# ODGIRON-v1_0-F103-0410.net
KiCad netlist of a schematic drawn in EAGLE
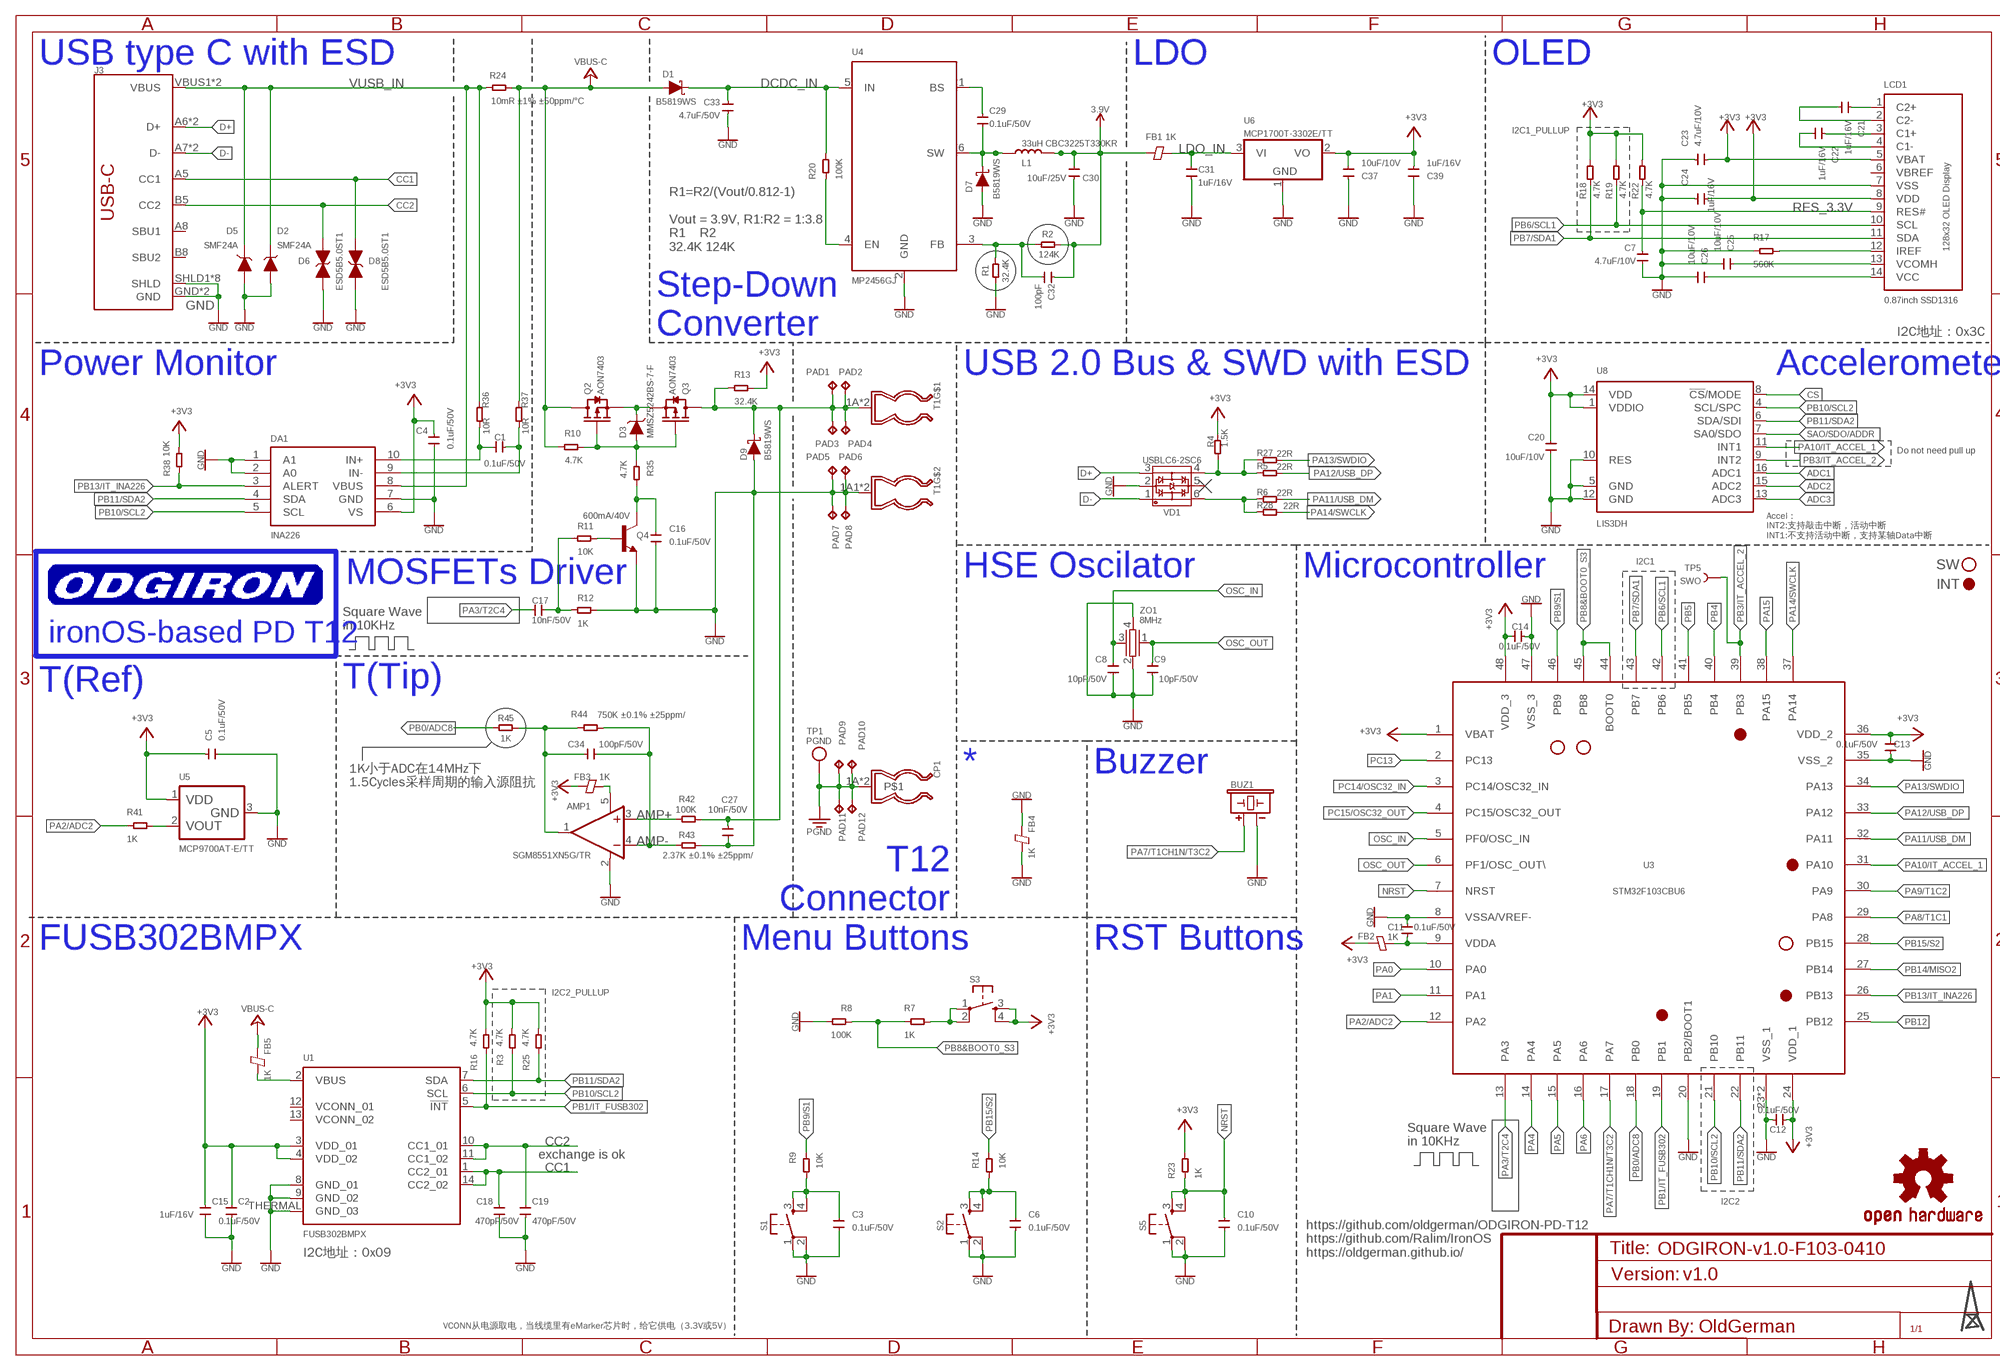
[diagram p0: schematic, sheet 1, part 1 of 2]
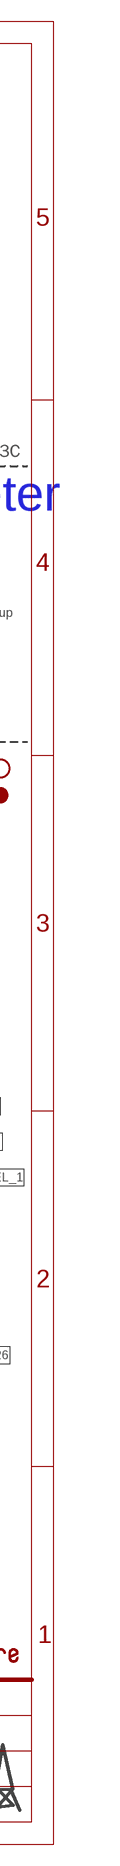
[diagram p1: schematic, sheet 1, part 2 of 2]

(export (version "E")
  (design (tool "Eeschema 10.0.6"))
  (components
    (comp (ref "AMP1")
      (value "SGM8551XN5G/TR")
      (footprint "eagle-import:SOT23-5")
      (fields (field (name "MPN") "OPA340NA/3KG4"))
      (libsource (lib "eagle-import") (part "AMP_SIMGLEN"))
    )
    (comp (ref "BUZ1")
      (value "BUZZERBUZZER_5020")
      (footprint "eagle-import:BUZZER_5020")
      (libsource (lib "eagle-import") (part "BUZZERBUZZER_5020"))
    )
    (comp (ref "C1")
      (value "0.1uF/50V")
      (footprint "eagle-import:C0603")
      (libsource (lib "eagle-import") (part "SEEED_CAP-0603"))
    )
    (comp (ref "C2")
      (value "0.1uF/50V")
      (footprint "eagle-import:C0603")
      (libsource (lib "eagle-import") (part "SEEED_CAP-0603"))
    )
    (comp (ref "C3")
      (value "0.1uF/50V")
      (footprint "eagle-import:C0603")
      (libsource (lib "eagle-import") (part "SEEED_CAP-0603"))
    )
    (comp (ref "C4")
      (value "0.1uF/50V")
      (footprint "eagle-import:C0603")
      (libsource (lib "eagle-import") (part "SEEED_CAP-0603"))
    )
    (comp (ref "C5")
      (value "0.1uF/50V")
      (footprint "eagle-import:C0603")
      (libsource (lib "eagle-import") (part "SEEED_CAP-0603"))
    )
    (comp (ref "C6")
      (value "0.1uF/50V")
      (footprint "eagle-import:C0603")
      (libsource (lib "eagle-import") (part "SEEED_CAP-0603"))
    )
    (comp (ref "C7")
      (value "4.7uF/10V")
      (footprint "eagle-import:C0603")
      (libsource (lib "eagle-import") (part "SEEED_CAP-0603"))
    )
    (comp (ref "C8")
      (value "10pF/50V")
      (footprint "eagle-import:C0603")
      (libsource (lib "eagle-import") (part "SEEED_CAP-0603"))
    )
    (comp (ref "C9")
      (value "10pF/50V")
      (footprint "eagle-import:C0603")
      (libsource (lib "eagle-import") (part "SEEED_CAP-0603"))
    )
    (comp (ref "C10")
      (value "0.1uF/50V")
      (footprint "eagle-import:C0603")
      (libsource (lib "eagle-import") (part "SEEED_CAP-0603"))
    )
    (comp (ref "C11")
      (value "0.1uF/50V")
      (footprint "eagle-import:C0603")
      (libsource (lib "eagle-import") (part "SEEED_CAP-0603"))
    )
    (comp (ref "C12")
      (value "0.1uF/50V")
      (footprint "eagle-import:C0603")
      (libsource (lib "eagle-import") (part "SEEED_CAP-0603"))
    )
    (comp (ref "C13")
      (value "0.1uF/50V")
      (footprint "eagle-import:C0603")
      (libsource (lib "eagle-import") (part "SEEED_CAP-0603"))
    )
    (comp (ref "C14")
      (value "0.1uF/50V")
      (footprint "eagle-import:C0603")
      (libsource (lib "eagle-import") (part "SEEED_CAP-0603"))
    )
    (comp (ref "C15")
      (value "1uF/16V")
      (footprint "eagle-import:C0603")
      (libsource (lib "eagle-import") (part "SEEED_CAP-0603"))
    )
    (comp (ref "C16")
      (value "0.1uF/50V")
      (footprint "eagle-import:C0603")
      (libsource (lib "eagle-import") (part "SEEED_CAP-0603"))
    )
    (comp (ref "C17")
      (value "10nF/50V")
      (footprint "eagle-import:C0603")
      (libsource (lib "eagle-import") (part "SEEED_CAP-0603"))
    )
    (comp (ref "C18")
      (value "470pF/50V")
      (footprint "eagle-import:C0603")
      (libsource (lib "eagle-import") (part "SEEED_CAP-0603"))
    )
    (comp (ref "C19")
      (value "470pF/50V")
      (footprint "eagle-import:C0603")
      (libsource (lib "eagle-import") (part "SEEED_CAP-0603"))
    )
    (comp (ref "C20")
      (value "10uF/10V")
      (footprint "eagle-import:C0603")
      (libsource (lib "eagle-import") (part "SEEED_CAP-0603"))
    )
    (comp (ref "C21")
      (value "1uF/16V")
      (footprint "eagle-import:C0603")
      (libsource (lib "eagle-import") (part "SEEED_CAP-0603"))
    )
    (comp (ref "C22")
      (value "1uF/16V")
      (footprint "eagle-import:C0603")
      (libsource (lib "eagle-import") (part "SEEED_CAP-0603"))
    )
    (comp (ref "C23")
      (value "4.7uF/10V")
      (footprint "eagle-import:C0603")
      (libsource (lib "eagle-import") (part "SEEED_CAP-0603"))
    )
    (comp (ref "C24")
      (value "1uF/16V")
      (footprint "eagle-import:C0603")
      (libsource (lib "eagle-import") (part "SEEED_CAP-0603"))
    )
    (comp (ref "C25")
      (value "10uF/10V")
      (footprint "eagle-import:C0603")
      (libsource (lib "eagle-import") (part "SEEED_CAP-0603"))
    )
    (comp (ref "C26")
      (value "10uF/10V")
      (footprint "eagle-import:C0603")
      (libsource (lib "eagle-import") (part "SEEED_CAP-0603"))
    )
    (comp (ref "C27")
      (value "10nF/50V")
      (footprint "eagle-import:C0603")
      (libsource (lib "eagle-import") (part "SEEED_CAP-0603"))
    )
    (comp (ref "C29")
      (value "0.1uF/50V")
      (footprint "eagle-import:C0603")
      (libsource (lib "eagle-import") (part "SEEED_CAP-0603"))
    )
    (comp (ref "C30")
      (value "10uF/25V")
      (footprint "eagle-import:C0805")
      (libsource (lib "eagle-import") (part "SEEED_CAP-0805"))
    )
    (comp (ref "C31")
      (value "1uF/16V")
      (footprint "eagle-import:C0603")
      (libsource (lib "eagle-import") (part "SEEED_CAP-0603"))
    )
    (comp (ref "C32")
      (value "100pF")
      (footprint "eagle-import:C0603")
      (libsource (lib "eagle-import") (part "SEEED_CAP-0603"))
    )
    (comp (ref "C33")
      (value "4.7uF/50V")
      (footprint "eagle-import:C0805")
      (libsource (lib "eagle-import") (part "SEEED_CAP-0805"))
    )
    (comp (ref "C34")
      (value "100pF/50V")
      (footprint "eagle-import:C0603")
      (libsource (lib "eagle-import") (part "SEEED_CAP-0603"))
    )
    (comp (ref "C37")
      (value "10uF/10V")
      (footprint "eagle-import:C0603")
      (libsource (lib "eagle-import") (part "SEEED_CAP-0603"))
    )
    (comp (ref "C39")
      (value "1uF/16V")
      (footprint "eagle-import:C0603")
      (libsource (lib "eagle-import") (part "SEEED_CAP-0603"))
    )
    (comp (ref "CP1")
      (value "FUSE_CLIPS_01")
      (footprint "eagle-import:FUSE_CLIPS_01")
      (libsource (lib "eagle-import") (part "FUSE_CLIPS_01"))
    )
    (comp (ref "D1")
      (value "B5819WS")
      (footprint "eagle-import:SOD-323")
      (libsource (lib "eagle-import") (part "DIODE_SCHOTTKYSOD323"))
    )
    (comp (ref "D2")
      (value "SMF24A")
      (footprint "eagle-import:SOD-123")
      (libsource (lib "eagle-import") (part "DIODE-TVS_UNIDIRECTIONALSOD-123"))
    )
    (comp (ref "D3")
      (value "MMSZ5242BS-7-F")
      (footprint "eagle-import:SOD-323")
      (libsource (lib "eagle-import") (part "DIODE_ZENERSOD-323"))
    )
    (comp (ref "D5")
      (value "SMF24A")
      (footprint "eagle-import:SOD-123")
      (libsource (lib "eagle-import") (part "DIODE-TVS_UNIDIRECTIONALSOD-123"))
    )
    (comp (ref "D6")
      (value "ESD5B5.0ST1")
      (footprint "eagle-import:SOD-523")
      (libsource (lib "eagle-import") (part "DIODE-TVS_BI−DIRECTIONALSOD-523"))
    )
    (comp (ref "D7")
      (value "B5819WS")
      (footprint "eagle-import:SOD-323")
      (libsource (lib "eagle-import") (part "DIODE_SCHOTTKYSOD323"))
    )
    (comp (ref "D8")
      (value "ESD5B5.0ST1")
      (footprint "eagle-import:SOD-523")
      (libsource (lib "eagle-import") (part "DIODE-TVS_BI−DIRECTIONALSOD-523"))
    )
    (comp (ref "D9")
      (value "B5819WS")
      (footprint "eagle-import:SOD-323")
      (libsource (lib "eagle-import") (part "DIODE_SCHOTTKYSOD323"))
    )
    (comp (ref "DA1")
      (value "INA226")
      (footprint "eagle-import:MSOP10")
      (libsource (lib "eagle-import") (part "INA226"))
    )
    (comp (ref "FB1")
      (value "1K")
      (footprint "eagle-import:F0603")
      (libsource (lib "eagle-import") (part "FERRITE-BEAD-0603"))
    )
    (comp (ref "FB2")
      (value "1K")
      (footprint "eagle-import:F0603")
      (libsource (lib "eagle-import") (part "FERRITE-BEAD-0603"))
    )
    (comp (ref "FB3")
      (value "1K")
      (footprint "eagle-import:F0603")
      (libsource (lib "eagle-import") (part "FERRITE-BEAD-0603"))
    )
    (comp (ref "FB4")
      (value "1K")
      (footprint "eagle-import:F0603")
      (libsource (lib "eagle-import") (part "FERRITE-BEAD-0603"))
    )
    (comp (ref "FB5")
      (value "1K")
      (footprint "eagle-import:F0603")
      (libsource (lib "eagle-import") (part "FERRITE-BEAD-0603"))
    )
    (comp (ref "J3")
      (value "USB_C_LONG-SYMBOL2-LAYER")
      (footprint "eagle-import:USB-C-16P")
      (libsource (lib "eagle-import") (part "USB_C_LONG-SYMBOL2-LAYER"))
    )
    (comp (ref "L1")
      (value "33uH CBC3225T330KR")
      (footprint "eagle-import:SMD,3.2X2.5X2.5MM")
      (libsource (lib "eagle-import") (part "INDUCTOR3225"))
    )
    (comp (ref "LCD1")
      (value "0.87inch SSD1316")
      (footprint "eagle-import:0.87INCH_128X32_OLED_SSD1306")
      (libsource (lib "eagle-import") (part "0.87INCH_OLED_128X32_SSD1306"))
    )
    (comp (ref "LOGO1")
      (value "OSHW-LOGONO_SILK")
      (footprint "eagle-import:DUMMY")
      (libsource (lib "eagle-import") (part "OSHW-LOGONO_SILK"))
    )
    (comp (ref "PAD1")
      (value "PADTP16SQ")
      (footprint "eagle-import:TP16SQ")
      (libsource (lib "eagle-import") (part "PADTP16SQ"))
    )
    (comp (ref "PAD2")
      (value "PADTP16SQ")
      (footprint "eagle-import:TP16SQ")
      (libsource (lib "eagle-import") (part "PADTP16SQ"))
    )
    (comp (ref "PAD3")
      (value "PADTP16SQ")
      (footprint "eagle-import:TP16SQ")
      (libsource (lib "eagle-import") (part "PADTP16SQ"))
    )
    (comp (ref "PAD4")
      (value "PADTP16SQ")
      (footprint "eagle-import:TP16SQ")
      (libsource (lib "eagle-import") (part "PADTP16SQ"))
    )
    (comp (ref "PAD5")
      (value "PADTP16SQ")
      (footprint "eagle-import:TP16SQ")
      (libsource (lib "eagle-import") (part "PADTP16SQ"))
    )
    (comp (ref "PAD6")
      (value "PADTP16SQ")
      (footprint "eagle-import:TP16SQ")
      (libsource (lib "eagle-import") (part "PADTP16SQ"))
    )
    (comp (ref "PAD7")
      (value "PADTP16SQ")
      (footprint "eagle-import:TP16SQ")
      (libsource (lib "eagle-import") (part "PADTP16SQ"))
    )
    (comp (ref "PAD8")
      (value "PADTP16SQ")
      (footprint "eagle-import:TP16SQ")
      (libsource (lib "eagle-import") (part "PADTP16SQ"))
    )
    (comp (ref "PAD9")
      (value "PADTP16SQ")
      (footprint "eagle-import:TP16SQ")
      (libsource (lib "eagle-import") (part "PADTP16SQ"))
    )
    (comp (ref "PAD10")
      (value "PADTP16SQ")
      (footprint "eagle-import:TP16SQ")
      (libsource (lib "eagle-import") (part "PADTP16SQ"))
    )
    (comp (ref "PAD11")
      (value "PADTP16SQ")
      (footprint "eagle-import:TP16SQ")
      (libsource (lib "eagle-import") (part "PADTP16SQ"))
    )
    (comp (ref "PAD12")
      (value "PADTP16SQ")
      (footprint "eagle-import:TP16SQ")
      (libsource (lib "eagle-import") (part "PADTP16SQ"))
    )
    (comp (ref "Q2")
      (value "AON7403")
      (footprint "eagle-import:DFN8P-0.65-3X3X0.8MM")
      (libsource (lib "eagle-import") (part "MOSFET-P-AON7403"))
    )
    (comp (ref "Q3")
      (value "AON7403")
      (footprint "eagle-import:DFN8P-0.65-3X3X0.8MM")
      (libsource (lib "eagle-import") (part "MOSFET-P-AON7403"))
    )
    (comp (ref "Q4")
      (value "600mA/40V")
      (footprint "eagle-import:SOT23-3")
      (libsource (lib "eagle-import") (part "TRANS_NPN-MMBT2222AL"))
    )
    (comp (ref "R1")
      (value "32.4K")
      (footprint "eagle-import:R0603")
      (libsource (lib "eagle-import") (part "SEEED_RES-0603"))
    )
    (comp (ref "R2")
      (value "124K")
      (footprint "eagle-import:R0603")
      (libsource (lib "eagle-import") (part "SEEED_RES-0603"))
    )
    (comp (ref "R3")
      (value "4.7K")
      (footprint "eagle-import:R0603")
      (libsource (lib "eagle-import") (part "SEEED_RES-0603"))
    )
    (comp (ref "R4")
      (value "1.5K")
      (footprint "eagle-import:R0603")
      (libsource (lib "eagle-import") (part "SEEED_RES-0603"))
    )
    (comp (ref "R5")
      (value "22R")
      (footprint "eagle-import:R0603")
      (libsource (lib "eagle-import") (part "SEEED_RES-0603"))
    )
    (comp (ref "R6")
      (value "22R")
      (footprint "eagle-import:R0603")
      (libsource (lib "eagle-import") (part "SEEED_RES-0603"))
    )
    (comp (ref "R7")
      (value "1K")
      (footprint "eagle-import:R0603")
      (libsource (lib "eagle-import") (part "SEEED_RES-0603"))
    )
    (comp (ref "R8")
      (value "100K")
      (footprint "eagle-import:R0603")
      (libsource (lib "eagle-import") (part "SEEED_RES-0603"))
    )
    (comp (ref "R9")
      (value "10K")
      (footprint "eagle-import:R0603")
      (libsource (lib "eagle-import") (part "SEEED_RES-0603"))
    )
    (comp (ref "R10")
      (value "4.7K")
      (footprint "eagle-import:R0603")
      (libsource (lib "eagle-import") (part "SEEED_RES-0603"))
    )
    (comp (ref "R11")
      (value "10K")
      (footprint "eagle-import:R0603")
      (libsource (lib "eagle-import") (part "SEEED_RES-0603"))
    )
    (comp (ref "R12")
      (value "1K")
      (footprint "eagle-import:R0603")
      (libsource (lib "eagle-import") (part "SEEED_RES-0603"))
    )
    (comp (ref "R13")
      (value "32.4K")
      (footprint "eagle-import:R0603")
      (libsource (lib "eagle-import") (part "SEEED_RES-0603"))
    )
    (comp (ref "R14")
      (value "10K")
      (footprint "eagle-import:R0603")
      (libsource (lib "eagle-import") (part "SEEED_RES-0603"))
    )
    (comp (ref "R16")
      (value "4.7K")
      (footprint "eagle-import:R0603")
      (libsource (lib "eagle-import") (part "SEEED_RES-0603"))
    )
    (comp (ref "R17")
      (value "560K")
      (footprint "eagle-import:R0603")
      (libsource (lib "eagle-import") (part "SEEED_RES-0603"))
    )
    (comp (ref "R18")
      (value "4.7K")
      (footprint "eagle-import:R0603")
      (libsource (lib "eagle-import") (part "SEEED_RES-0603"))
    )
    (comp (ref "R19")
      (value "4.7K")
      (footprint "eagle-import:R0603")
      (libsource (lib "eagle-import") (part "SEEED_RES-0603"))
    )
    (comp (ref "R20")
      (value "100K")
      (footprint "eagle-import:R0603")
      (libsource (lib "eagle-import") (part "SEEED_RES-0603"))
    )
    (comp (ref "R22")
      (value "4.7K")
      (footprint "eagle-import:R0603")
      (libsource (lib "eagle-import") (part "SEEED_RES-0603"))
    )
    (comp (ref "R23")
      (value "1K")
      (footprint "eagle-import:R0603")
      (libsource (lib "eagle-import") (part "SEEED_RES-0603"))
    )
    (comp (ref "R24")
      (value "10mR ±1% ±50ppm/°C")
      (footprint "eagle-import:R1206")
      (libsource (lib "eagle-import") (part "SEEED_RES-1206"))
    )
    (comp (ref "R25")
      (value "4.7K")
      (footprint "eagle-import:R0603")
      (libsource (lib "eagle-import") (part "SEEED_RES-0603"))
    )
    (comp (ref "R27")
      (value "22R")
      (footprint "eagle-import:R0603")
      (libsource (lib "eagle-import") (part "SEEED_RES-0603"))
    )
    (comp (ref "R28")
      (value "22R")
      (footprint "eagle-import:R0603")
      (libsource (lib "eagle-import") (part "SEEED_RES-0603"))
    )
    (comp (ref "R35")
      (value "4.7K")
      (footprint "eagle-import:R0603")
      (libsource (lib "eagle-import") (part "SEEED_RES-0603"))
    )
    (comp (ref "R36")
      (value "10R")
      (footprint "eagle-import:R0603")
      (libsource (lib "eagle-import") (part "SEEED_RES-0603"))
    )
    (comp (ref "R37")
      (value "10R")
      (footprint "eagle-import:R0603")
      (libsource (lib "eagle-import") (part "SEEED_RES-0603"))
    )
    (comp (ref "R38")
      (value "10K")
      (footprint "eagle-import:R0603")
      (libsource (lib "eagle-import") (part "SEEED_RES-0603"))
    )
    (comp (ref "R41")
      (value "1K")
      (footprint "eagle-import:R0603")
      (libsource (lib "eagle-import") (part "SEEED_RES-0603"))
    )
    (comp (ref "R42")
      (value "100K")
      (footprint "eagle-import:R0603")
      (libsource (lib "eagle-import") (part "SEEED_RES-0603"))
    )
    (comp (ref "R43")
      (value "2.37K ±0.1% ±25ppm/℃")
      (footprint "eagle-import:R0603")
      (libsource (lib "eagle-import") (part "SEEED_RES-0603"))
    )
    (comp (ref "R44")
      (value "750K ±0.1% ±25ppm/℃")
      (footprint "eagle-import:R0603")
      (libsource (lib "eagle-import") (part "SEEED_RES-0603"))
    )
    (comp (ref "R45")
      (value "1K")
      (footprint "eagle-import:R0603")
      (libsource (lib "eagle-import") (part "SEEED_RES-0603"))
    )
    (comp (ref "S1")
      (value "TAC_SWITCHSMD")
      (footprint "eagle-import:TACTILE_SWITCH_SMD")
      (libsource (lib "eagle-import") (part "TAC_SWITCHSMD"))
    )
    (comp (ref "S2")
      (value "TAC_SWITCHSMD")
      (footprint "eagle-import:TACTILE_SWITCH_SMD")
      (libsource (lib "eagle-import") (part "TAC_SWITCHSMD"))
    )
    (comp (ref "S3")
      (value "TAC_SWITCHSMD")
      (footprint "eagle-import:TACTILE_SWITCH_SMD")
      (libsource (lib "eagle-import") (part "TAC_SWITCHSMD"))
    )
    (comp (ref "S5")
      (value "TAC_SWITCHSMD")
      (footprint "eagle-import:TACTILE_SWITCH_SMD")
      (libsource (lib "eagle-import") (part "untitled_TAC_SWITCHSMD"))
    )
    (comp (ref "T1")
      (value "HAKKO_T12_K-TYPE_WITH_FUSE_CLIPS_X2")
      (footprint "eagle-import:HAKKO_T12_K-TYPE_WITH_FUSE_CLIPS_X2")
      (libsource (lib "eagle-import") (part "HAKKO_T12_K-TYPE_WITH_FUSE_CLIPS_X2"))
    )
    (comp (ref "TP1")
      (value "PGND")
      (footprint "eagle-import:TESTPOINT_ROUND_2MM")
      (libsource (lib "eagle-import") (part "TESTPOINTROUND2MM"))
    )
    (comp (ref "TP5")
      (value "SWO")
      (footprint "eagle-import:PAD.03X.03")
      (libsource (lib "eagle-import") (part "TEST-POINT3"))
    )
    (comp (ref "U1")
      (value "FUSB302BMPX")
      (footprint "eagle-import:QFN14-2.5X2.5MM")
      (libsource (lib "eagle-import") (part "FUSB302"))
    )
    (comp (ref "U3")
      (value "STM32F103CBU6")
      (footprint "eagle-import:QFN48_7X7MM_0.5MM")
      (libsource (lib "eagle-import") (part "STM32F1_QFN48"))
    )
    (comp (ref "U4")
      (value "MP2456GJ")
      (footprint "eagle-import:SOT23-6")
      (libsource (lib "eagle-import") (part "MP2456"))
    )
    (comp (ref "U5")
      (value "MCP9700AT-E/TT")
      (footprint "eagle-import:SOT23-3@1")
      (libsource (lib "eagle-import") (part "MCP9700"))
    )
    (comp (ref "U6")
      (value "MCP1700T-3302E/TT")
      (footprint "eagle-import:SOT23-3")
      (libsource (lib "eagle-import") (part "MCP1700"))
    )
    (comp (ref "U8")
      (value "LIS3DH")
      (footprint "eagle-import:LGA-16-3X3")
      (libsource (lib "eagle-import") (part "LIS3DH"))
    )
    (comp (ref "VD1")
      (value "USBLC6-2SC6")
      (footprint "eagle-import:SOT23-6")
      (libsource (lib "eagle-import") (part "USBLC6-2SOT23-6"))
    )
    (comp (ref "ZO1")
      (value "8MHz")
      (footprint "eagle-import:3.2X2.5_KX-7")
      (libsource (lib "eagle-import") (part "3225_CRYSTALL"))
    )
  )
  (nets
    (net (code "1") (name "+3V3") (class "Default")
      (node (ref "C12") (pin "2") (pinfunction "P$2_2") (pintype "passive"))
      (node (ref "C13") (pin "2") (pinfunction "P$2_2") (pintype "passive"))
      (node (ref "C14") (pin "2") (pinfunction "P$2_2") (pintype "passive"))
      (node (ref "C15") (pin "1") (pinfunction "P$1_1") (pintype "passive"))
      (node (ref "C2") (pin "1") (pinfunction "P$1_1") (pintype "passive"))
      (node (ref "C20") (pin "2") (pinfunction "P$2_2") (pintype "passive"))
      (node (ref "C23") (pin "2") (pinfunction "P$2_2") (pintype "passive"))
      (node (ref "C24") (pin "2") (pinfunction "P$2_2") (pintype "passive"))
      (node (ref "C37") (pin "2") (pinfunction "P$2_2") (pintype "passive"))
      (node (ref "C39") (pin "2") (pinfunction "P$2_2") (pintype "passive"))
      (node (ref "C4") (pin "1") (pinfunction "P$1_1") (pintype "passive"))
      (node (ref "C5") (pin "1") (pinfunction "P$1_1") (pintype "passive"))
      (node (ref "DA1") (pin "6") (pinfunction "VS_6") (pintype "bidirectional"))
      (node (ref "FB2") (pin "2") (pinfunction "2_2") (pintype "bidirectional"))
      (node (ref "FB3") (pin "2") (pinfunction "2_2") (pintype "bidirectional"))
      (node (ref "LCD1") (pin "5") (pinfunction "VBAT_5") (pintype "power_in"))
      (node (ref "LCD1") (pin "8") (pinfunction "VDD_8") (pintype "power_in"))
      (node (ref "R13") (pin "2") (pinfunction "2_2") (pintype "passive"))
      (node (ref "R16") (pin "1") (pinfunction "1_1") (pintype "passive"))
      (node (ref "R18") (pin "2") (pinfunction "2_2") (pintype "passive"))
      (node (ref "R19") (pin "2") (pinfunction "2_2") (pintype "passive"))
      (node (ref "R22") (pin "2") (pinfunction "2_2") (pintype "passive"))
      (node (ref "R23") (pin "2") (pinfunction "2_2") (pintype "passive"))
      (node (ref "R25") (pin "1") (pinfunction "1_1") (pintype "passive"))
      (node (ref "R3") (pin "1") (pinfunction "1_1") (pintype "passive"))
      (node (ref "R38") (pin "1") (pinfunction "1_1") (pintype "passive"))
      (node (ref "R4") (pin "2") (pinfunction "2_2") (pintype "passive"))
      (node (ref "S3") (pin "3") (pinfunction "3_3") (pintype "passive"))
      (node (ref "S3") (pin "4") (pinfunction "4_4") (pintype "passive"))
      (node (ref "U1") (pin "3") (pinfunction "VDD_01_3") (pintype "bidirectional"))
      (node (ref "U1") (pin "4") (pinfunction "VDD_02_4") (pintype "bidirectional"))
      (node (ref "U3") (pin "1") (pinfunction "VBAT_1") (pintype "bidirectional"))
      (node (ref "U3") (pin "24") (pinfunction "VDD_1_24") (pintype "bidirectional"))
      (node (ref "U3") (pin "36") (pinfunction "VDD_2_36") (pintype "bidirectional"))
      (node (ref "U3") (pin "48") (pinfunction "VDD_3_48") (pintype "bidirectional"))
      (node (ref "U5") (pin "1") (pinfunction "VDD_1") (pintype "input"))
      (node (ref "U6") (pin "2") (pinfunction "VO_2") (pintype "passive"))
      (node (ref "U8") (pin "1") (pinfunction "VDDIO_1") (pintype "bidirectional"))
      (node (ref "U8") (pin "14") (pinfunction "VDD_14") (pintype "bidirectional"))
    )
    (net (code "2") (name "/AMP+") (class "Default")
      (node (ref "AMP1") (pin "3") (pinfunction "+IN_3") (pintype "input"))
      (node (ref "R42") (pin "1") (pinfunction "1_1") (pintype "passive"))
    )
    (net (code "3") (name "/AMP-") (class "Default")
      (node (ref "AMP1") (pin "4") (pinfunction "-IN_4") (pintype "input"))
      (node (ref "C34") (pin "2") (pinfunction "P$2_2") (pintype "passive"))
      (node (ref "R43") (pin "1") (pinfunction "1_1") (pintype "passive"))
      (node (ref "R44") (pin "2") (pinfunction "2_2") (pintype "passive"))
    )
    (net (code "4") (name "/DCDC_IN") (class "Default")
      (node (ref "C33") (pin "1") (pinfunction "P$1_1") (pintype "passive"))
      (node (ref "D1") (pin "C") (pinfunction "C_C") (pintype "passive"))
      (node (ref "R20") (pin "2") (pinfunction "2_2") (pintype "passive"))
      (node (ref "U4") (pin "5") (pinfunction "IN_5") (pintype "bidirectional"))
    )
    (net (code "5") (name "/LDO_IN") (class "Default")
      (node (ref "C31") (pin "2") (pinfunction "P$2_2") (pintype "passive"))
      (node (ref "FB1") (pin "2") (pinfunction "2_2") (pintype "bidirectional"))
      (node (ref "U6") (pin "3") (pinfunction "VI_3") (pintype "input"))
    )
    (net (code "6") (name "/RES_3.3V") (class "Default")
      (node (ref "C7") (pin "1") (pinfunction "P$1_1") (pintype "passive"))
      (node (ref "LCD1") (pin "9") (pinfunction "RES#_9") (pintype "bidirectional"))
      (node (ref "R22") (pin "1") (pinfunction "1_1") (pintype "passive"))
    )
    (net (code "7") (name "/VBREF") (class "Default")
      (node (ref "LCD1") (pin "6") (pinfunction "VBREF_6") (pintype "power_in"))
    )
    (net (code "8") (name "/VUSB_IN") (class "Default")
      (node (ref "D2") (pin "C") (pinfunction "K_C") (pintype "passive"))
      (node (ref "D5") (pin "C") (pinfunction "K_C") (pintype "passive"))
      (node (ref "DA1") (pin "8") (pinfunction "VBUS_8") (pintype "bidirectional"))
      (node (ref "J3") (pin "VBUS1") (pinfunction "VBUS_VBUS1") (pintype "bidirectional"))
      (node (ref "J3") (pin "VBUS2") (pinfunction "VBUS_VBUS2") (pintype "bidirectional"))
      (node (ref "R24") (pin "2") (pinfunction "2_2") (pintype "passive"))
      (node (ref "R36") (pin "2") (pinfunction "2_2") (pintype "passive"))
    )
    (net (code "9") (name "3.9V") (class "Default")
      (node (ref "C30") (pin "1") (pinfunction "P$1_1") (pintype "passive"))
      (node (ref "C32") (pin "1") (pinfunction "P$1_1") (pintype "passive"))
      (node (ref "FB1") (pin "1") (pinfunction "1_1") (pintype "bidirectional"))
      (node (ref "L1") (pin "2") (pinfunction "2_2") (pintype "passive"))
      (node (ref "R2") (pin "1") (pinfunction "1_1") (pintype "passive"))
    )
    (net (code "10") (name "ADC1") (class "Default")
      (node (ref "U8") (pin "16") (pinfunction "ADC1_16") (pintype "bidirectional"))
    )
    (net (code "11") (name "ADC2") (class "Default")
      (node (ref "U8") (pin "15") (pinfunction "ADC2_15") (pintype "bidirectional"))
    )
    (net (code "12") (name "ADC3") (class "Default")
      (node (ref "U8") (pin "13") (pinfunction "ADC3_13") (pintype "bidirectional"))
    )
    (net (code "13") (name "CC1") (class "Default")
      (node (ref "C18") (pin "1") (pinfunction "P$1_1") (pintype "passive"))
      (node (ref "D8") (pin "K") (pinfunction "C_K") (pintype "passive"))
      (node (ref "J3") (pin "A5") (pinfunction "CC1_A5") (pintype "bidirectional"))
      (node (ref "U1") (pin "1") (pinfunction "CC2_01_1") (pintype "bidirectional"))
      (node (ref "U1") (pin "14") (pinfunction "CC2_02_14") (pintype "bidirectional"))
    )
    (net (code "14") (name "CC2") (class "Default")
      (node (ref "C19") (pin "1") (pinfunction "P$1_1") (pintype "passive"))
      (node (ref "D6") (pin "K") (pinfunction "C_K") (pintype "passive"))
      (node (ref "J3") (pin "B5") (pinfunction "CC2_B5") (pintype "bidirectional"))
      (node (ref "U1") (pin "10") (pinfunction "CC1_01_10") (pintype "bidirectional"))
      (node (ref "U1") (pin "11") (pinfunction "CC1_02_11") (pintype "bidirectional"))
    )
    (net (code "15") (name "CS") (class "Default")
      (node (ref "U8") (pin "8") (pinfunction "~{CS}/MODE_8") (pintype "bidirectional"))
    )
    (net (code "16") (name "D+") (class "Default")
      (node (ref "J3") (pin "A6") (pinfunction "D+_A6") (pintype "bidirectional"))
      (node (ref "J3") (pin "B6") (pinfunction "D+_B6") (pintype "bidirectional"))
      (node (ref "VD1") (pin "3") (pinfunction "P$3_3") (pintype "bidirectional"))
    )
    (net (code "17") (name "D-") (class "Default")
      (node (ref "J3") (pin "A7") (pinfunction "D-_A7") (pintype "bidirectional"))
      (node (ref "J3") (pin "B7") (pinfunction "D-_B7") (pintype "bidirectional"))
      (node (ref "VD1") (pin "1") (pinfunction "P$1_1") (pintype "bidirectional"))
    )
    (net (code "18") (name "GND") (class "Default")
      (node (ref "AMP1") (pin "2") (pinfunction "V-_2") (pintype "power_in"))
      (node (ref "BUZ1") (pin "-") (pinfunction "LEAD-_-") (pintype "passive"))
      (node (ref "C10") (pin "2") (pinfunction "P$2_2") (pintype "passive"))
      (node (ref "C11") (pin "1") (pinfunction "P$1_1") (pintype "passive"))
      (node (ref "C12") (pin "1") (pinfunction "P$1_1") (pintype "passive"))
      (node (ref "C13") (pin "1") (pinfunction "P$1_1") (pintype "passive"))
      (node (ref "C14") (pin "1") (pinfunction "P$1_1") (pintype "passive"))
      (node (ref "C15") (pin "2") (pinfunction "P$2_2") (pintype "passive"))
      (node (ref "C16") (pin "1") (pinfunction "P$1_1") (pintype "passive"))
      (node (ref "C18") (pin "2") (pinfunction "P$2_2") (pintype "passive"))
      (node (ref "C19") (pin "2") (pinfunction "P$2_2") (pintype "passive"))
      (node (ref "C2") (pin "2") (pinfunction "P$2_2") (pintype "passive"))
      (node (ref "C20") (pin "1") (pinfunction "P$1_1") (pintype "passive"))
      (node (ref "C23") (pin "1") (pinfunction "P$1_1") (pintype "passive"))
      (node (ref "C24") (pin "1") (pinfunction "P$1_1") (pintype "passive"))
      (node (ref "C25") (pin "2") (pinfunction "P$2_2") (pintype "passive"))
      (node (ref "C26") (pin "2") (pinfunction "P$2_2") (pintype "passive"))
      (node (ref "C27") (pin "2") (pinfunction "P$2_2") (pintype "passive"))
      (node (ref "C3") (pin "2") (pinfunction "P$2_2") (pintype "passive"))
      (node (ref "C30") (pin "2") (pinfunction "P$2_2") (pintype "passive"))
      (node (ref "C31") (pin "1") (pinfunction "P$1_1") (pintype "passive"))
      (node (ref "C33") (pin "2") (pinfunction "P$2_2") (pintype "passive"))
      (node (ref "C37") (pin "1") (pinfunction "P$1_1") (pintype "passive"))
      (node (ref "C39") (pin "1") (pinfunction "P$1_1") (pintype "passive"))
      (node (ref "C4") (pin "2") (pinfunction "P$2_2") (pintype "passive"))
      (node (ref "C5") (pin "2") (pinfunction "P$2_2") (pintype "passive"))
      (node (ref "C6") (pin "2") (pinfunction "P$2_2") (pintype "passive"))
      (node (ref "C7") (pin "2") (pinfunction "P$2_2") (pintype "passive"))
      (node (ref "C8") (pin "1") (pinfunction "P$1_1") (pintype "passive"))
      (node (ref "C9") (pin "1") (pinfunction "P$1_1") (pintype "passive"))
      (node (ref "D2") (pin "A") (pinfunction "A_A") (pintype "passive"))
      (node (ref "D5") (pin "A") (pinfunction "A_A") (pintype "passive"))
      (node (ref "D6") (pin "A") (pinfunction "A_A") (pintype "passive"))
      (node (ref "D7") (pin "A") (pinfunction "A_A") (pintype "passive"))
      (node (ref "D8") (pin "A") (pinfunction "A_A") (pintype "passive"))
      (node (ref "D9") (pin "A") (pinfunction "A_A") (pintype "passive"))
      (node (ref "DA1") (pin "1") (pinfunction "A1_1") (pintype "bidirectional"))
      (node (ref "DA1") (pin "2") (pinfunction "A0_2") (pintype "bidirectional"))
      (node (ref "DA1") (pin "7") (pinfunction "GND_7") (pintype "bidirectional"))
      (node (ref "FB4") (pin "1") (pinfunction "1_1") (pintype "bidirectional"))
      (node (ref "FB4") (pin "2") (pinfunction "2_2") (pintype "bidirectional"))
      (node (ref "J3") (pin "GND") (pinfunction "GND_GND") (pintype "bidirectional"))
      (node (ref "J3") (pin "GND2") (pinfunction "GND_GND2") (pintype "bidirectional"))
      (node (ref "J3") (pin "SHLD1") (pinfunction "SHLD_SHLD1") (pintype "bidirectional"))
      (node (ref "J3") (pin "SHLD2") (pinfunction "SHLD_SHLD2") (pintype "bidirectional"))
      (node (ref "J3") (pin "SHLD3") (pinfunction "SHLD_SHLD3") (pintype "bidirectional"))
      (node (ref "J3") (pin "SHLD4") (pinfunction "SHLD_SHLD4") (pintype "bidirectional"))
      (node (ref "J3") (pin "SHLD5") (pinfunction "SHLD_SHLD5") (pintype "bidirectional"))
      (node (ref "J3") (pin "SHLD6") (pinfunction "SHLD_SHLD6") (pintype "bidirectional"))
      (node (ref "J3") (pin "SHLD7") (pinfunction "SHLD_SHLD7") (pintype "bidirectional"))
      (node (ref "J3") (pin "SHLD8") (pinfunction "SHLD_SHLD8") (pintype "bidirectional"))
      (node (ref "LCD1") (pin "7") (pinfunction "VSS_7") (pintype "power_in"))
      (node (ref "PAD5") (pin "TP") (pinfunction "TP_TP") (pintype "input"))
      (node (ref "PAD6") (pin "TP") (pinfunction "TP_TP") (pintype "input"))
      (node (ref "PAD7") (pin "TP") (pinfunction "TP_TP") (pintype "input"))
      (node (ref "PAD8") (pin "TP") (pinfunction "TP_TP") (pintype "input"))
      (node (ref "Q4") (pin "2") (pinfunction "E_2") (pintype "passive"))
      (node (ref "R1") (pin "1") (pinfunction "1_1") (pintype "passive"))
      (node (ref "R12") (pin "1") (pinfunction "1_1") (pintype "passive"))
      (node (ref "R17") (pin "1") (pinfunction "1_1") (pintype "passive"))
      (node (ref "R43") (pin "2") (pinfunction "2_2") (pintype "passive"))
      (node (ref "R8") (pin "2") (pinfunction "2_2") (pintype "passive"))
      (node (ref "S1") (pin "1") (pinfunction "1_1") (pintype "passive"))
      (node (ref "S1") (pin "2") (pinfunction "2_2") (pintype "passive"))
      (node (ref "S2") (pin "1") (pinfunction "1_1") (pintype "passive"))
      (node (ref "S2") (pin "2") (pinfunction "2_2") (pintype "passive"))
      (node (ref "S5") (pin "1") (pinfunction "1_1") (pintype "passive"))
      (node (ref "S5") (pin "2") (pinfunction "2_2") (pintype "passive"))
      (node (ref "T1") (pin "1A1") (pinfunction "P$1_1A1") (pintype "bidirectional"))
      (node (ref "T1") (pin "1B1") (pinfunction "P$1_1B1") (pintype "bidirectional"))
      (node (ref "U1") (pin "8") (pinfunction "GND_01_8") (pintype "bidirectional"))
      (node (ref "U1") (pin "9") (pinfunction "GND_02_9") (pintype "bidirectional"))
      (node (ref "U1") (pin "THERMAL") (pinfunction "GND_03_THERMAL") (pintype "bidirectional"))
      (node (ref "U3") (pin "20") (pinfunction "PB2/BOOT1_20") (pintype "bidirectional"))
      (node (ref "U3") (pin "23") (pinfunction "VSS_1_23") (pintype "bidirectional"))
      (node (ref "U3") (pin "35") (pinfunction "VSS_2_35") (pintype "bidirectional"))
      (node (ref "U3") (pin "47") (pinfunction "VSS_3_47") (pintype "bidirectional"))
      (node (ref "U3") (pin "8") (pinfunction "VSSA/VREF-_8") (pintype "bidirectional"))
      (node (ref "U3") (pin "P$1") (pinfunction "VSS_1_P$1") (pintype "bidirectional"))
      (node (ref "U4") (pin "2") (pinfunction "GND_2") (pintype "bidirectional"))
      (node (ref "U5") (pin "3") (pinfunction "GND_3") (pintype "passive"))
      (node (ref "U6") (pin "1") (pinfunction "GND_1") (pintype "passive"))
      (node (ref "U8") (pin "10") (pinfunction "RES_10") (pintype "bidirectional"))
      (node (ref "U8") (pin "12") (pinfunction "GND_12") (pintype "bidirectional"))
      (node (ref "U8") (pin "5") (pinfunction "GND_5") (pintype "bidirectional"))
      (node (ref "VD1") (pin "2") (pinfunction "P$2_2") (pintype "bidirectional"))
      (node (ref "ZO1") (pin "2") (pinfunction "P$3_2") (pintype "power_in"))
      (node (ref "ZO1") (pin "4") (pinfunction "P$4_4") (pintype "power_in"))
    )
    (net (code "19") (name "NRST") (class "Default")
      (node (ref "C10") (pin "1") (pinfunction "P$1_1") (pintype "passive"))
      (node (ref "R23") (pin "1") (pinfunction "1_1") (pintype "passive"))
      (node (ref "S5") (pin "3") (pinfunction "3_3") (pintype "passive"))
      (node (ref "S5") (pin "4") (pinfunction "4_4") (pintype "passive"))
      (node (ref "U3") (pin "7") (pinfunction "NRST_7") (pintype "bidirectional"))
    )
    (net (code "20") (name "Net-(AMP1-OUT)") (class "Default")
      (node (ref "AMP1") (pin "1") (pinfunction "OUT_1") (pintype "output"))
      (node (ref "C34") (pin "1") (pinfunction "P$1_1") (pintype "passive"))
      (node (ref "R44") (pin "1") (pinfunction "1_1") (pintype "passive"))
      (node (ref "R45") (pin "2") (pinfunction "2_2") (pintype "passive"))
    )
    (net (code "21") (name "Net-(AMP1-V+)") (class "Default")
      (node (ref "AMP1") (pin "5") (pinfunction "V+_5") (pintype "power_in"))
      (node (ref "FB3") (pin "1") (pinfunction "1_1") (pintype "bidirectional"))
    )
    (net (code "22") (name "Net-(C1-P$1)") (class "Default")
      (node (ref "C1") (pin "1") (pinfunction "P$1_1") (pintype "passive"))
      (node (ref "DA1") (pin "10") (pinfunction "IN+_10") (pintype "bidirectional"))
      (node (ref "R36") (pin "1") (pinfunction "1_1") (pintype "passive"))
    )
    (net (code "23") (name "Net-(C1-P$2)") (class "Default")
      (node (ref "C1") (pin "2") (pinfunction "P$2_2") (pintype "passive"))
      (node (ref "DA1") (pin "9") (pinfunction "IN-_9") (pintype "bidirectional"))
      (node (ref "R37") (pin "1") (pinfunction "1_1") (pintype "passive"))
    )
    (net (code "24") (name "Net-(C3-P$1)") (class "Default")
      (node (ref "C3") (pin "1") (pinfunction "P$1_1") (pintype "passive"))
      (node (ref "R9") (pin "2") (pinfunction "2_2") (pintype "passive"))
      (node (ref "S1") (pin "3") (pinfunction "3_3") (pintype "passive"))
      (node (ref "S1") (pin "4") (pinfunction "4_4") (pintype "passive"))
    )
    (net (code "25") (name "Net-(C6-P$1)") (class "Default")
      (node (ref "C6") (pin "1") (pinfunction "P$1_1") (pintype "passive"))
      (node (ref "R14") (pin "2") (pinfunction "2_2") (pintype "passive"))
      (node (ref "S2") (pin "3") (pinfunction "3_3") (pintype "passive"))
      (node (ref "S2") (pin "4") (pinfunction "4_4") (pintype "passive"))
    )
    (net (code "26") (name "Net-(C11-P$2)") (class "Default")
      (node (ref "C11") (pin "2") (pinfunction "P$2_2") (pintype "passive"))
      (node (ref "FB2") (pin "1") (pinfunction "1_1") (pintype "bidirectional"))
      (node (ref "U3") (pin "9") (pinfunction "VDDA_9") (pintype "bidirectional"))
    )
    (net (code "27") (name "Net-(C16-P$2)") (class "Default")
      (node (ref "C16") (pin "2") (pinfunction "P$2_2") (pintype "passive"))
      (node (ref "Q4") (pin "3") (pinfunction "C_3") (pintype "passive"))
      (node (ref "R35") (pin "2") (pinfunction "2_2") (pintype "passive"))
    )
    (net (code "28") (name "Net-(C17-P$1)") (class "Default")
      (node (ref "C17") (pin "1") (pinfunction "P$1_1") (pintype "passive"))
      (node (ref "R11") (pin "2") (pinfunction "2_2") (pintype "passive"))
      (node (ref "R12") (pin "2") (pinfunction "2_2") (pintype "passive"))
    )
    (net (code "29") (name "Net-(C21-P$1)") (class "Default")
      (node (ref "C21") (pin "1") (pinfunction "P$1_1") (pintype "passive"))
      (node (ref "LCD1") (pin "1") (pinfunction "C2+_1") (pintype "bidirectional"))
    )
    (net (code "30") (name "Net-(C21-P$2)") (class "Default")
      (node (ref "C21") (pin "2") (pinfunction "P$2_2") (pintype "passive"))
      (node (ref "LCD1") (pin "2") (pinfunction "C2-_2") (pintype "bidirectional"))
    )
    (net (code "31") (name "Net-(C22-P$1)") (class "Default")
      (node (ref "C22") (pin "1") (pinfunction "P$1_1") (pintype "passive"))
      (node (ref "LCD1") (pin "3") (pinfunction "C1+_3") (pintype "bidirectional"))
    )
    (net (code "32") (name "Net-(C22-P$2)") (class "Default")
      (node (ref "C22") (pin "2") (pinfunction "P$2_2") (pintype "passive"))
      (node (ref "LCD1") (pin "4") (pinfunction "C1-_4") (pintype "bidirectional"))
    )
    (net (code "33") (name "Net-(C25-P$1)") (class "Default")
      (node (ref "C25") (pin "1") (pinfunction "P$1_1") (pintype "passive"))
      (node (ref "LCD1") (pin "13") (pinfunction "VCOMH_13") (pintype "power_in"))
    )
    (net (code "34") (name "Net-(C26-P$1)") (class "Default")
      (node (ref "C26") (pin "1") (pinfunction "P$1_1") (pintype "passive"))
      (node (ref "LCD1") (pin "14") (pinfunction "VCC_14") (pintype "power_in"))
    )
    (net (code "35") (name "Net-(C27-P$1)") (class "Default")
      (node (ref "C27") (pin "1") (pinfunction "P$1_1") (pintype "passive"))
      (node (ref "D9") (pin "C") (pinfunction "C_C") (pintype "passive"))
      (node (ref "PAD1") (pin "TP") (pinfunction "TP_TP") (pintype "input"))
      (node (ref "PAD2") (pin "TP") (pinfunction "TP_TP") (pintype "input"))
      (node (ref "PAD3") (pin "TP") (pinfunction "TP_TP") (pintype "input"))
      (node (ref "PAD4") (pin "TP") (pinfunction "TP_TP") (pintype "input"))
      (node (ref "Q3") (pin "5") (pinfunction "D_5") (pintype "passive"))
      (node (ref "Q3") (pin "6") (pinfunction "D_6") (pintype "passive"))
      (node (ref "Q3") (pin "7") (pinfunction "D_7") (pintype "passive"))
      (node (ref "Q3") (pin "8") (pinfunction "D_8") (pintype "passive"))
      (node (ref "Q3") (pin "9") (pinfunction "D_9") (pintype "passive"))
      (node (ref "R13") (pin "1") (pinfunction "1_1") (pintype "passive"))
      (node (ref "R42") (pin "2") (pinfunction "2_2") (pintype "passive"))
      (node (ref "T1") (pin "1A") (pinfunction "P$1_1A") (pintype "bidirectional"))
      (node (ref "T1") (pin "1B") (pinfunction "P$1_1B") (pintype "bidirectional"))
    )
    (net (code "36") (name "Net-(C29-P$1)") (class "Default")
      (node (ref "C29") (pin "1") (pinfunction "P$1_1") (pintype "passive"))
      (node (ref "U4") (pin "1") (pinfunction "BS_1") (pintype "bidirectional"))
    )
    (net (code "37") (name "Net-(C29-P$2)") (class "Default")
      (node (ref "C29") (pin "2") (pinfunction "P$2_2") (pintype "passive"))
      (node (ref "D7") (pin "C") (pinfunction "C_C") (pintype "passive"))
      (node (ref "L1") (pin "1") (pinfunction "1_1") (pintype "passive"))
      (node (ref "U4") (pin "6") (pinfunction "SW_6") (pintype "bidirectional"))
    )
    (net (code "38") (name "Net-(C32-P$2)") (class "Default")
      (node (ref "C32") (pin "2") (pinfunction "P$2_2") (pintype "passive"))
      (node (ref "R1") (pin "2") (pinfunction "2_2") (pintype "passive"))
      (node (ref "R2") (pin "2") (pinfunction "2_2") (pintype "passive"))
      (node (ref "U4") (pin "3") (pinfunction "FB_3") (pintype "bidirectional"))
    )
    (net (code "39") (name "Net-(D3-PadC)") (class "Default")
      (node (ref "D3") (pin "C") (pinfunction "C_C") (pintype "passive"))
      (node (ref "Q2") (pin "1") (pinfunction "S_1") (pintype "passive"))
      (node (ref "Q2") (pin "2") (pinfunction "S_2") (pintype "passive"))
      (node (ref "Q2") (pin "3") (pinfunction "S_3") (pintype "passive"))
      (node (ref "Q3") (pin "1") (pinfunction "S_1") (pintype "passive"))
      (node (ref "Q3") (pin "2") (pinfunction "S_2") (pintype "passive"))
      (node (ref "Q3") (pin "3") (pinfunction "S_3") (pintype "passive"))
    )
    (net (code "40") (name "Net-(LCD1-IREF)") (class "Default")
      (node (ref "LCD1") (pin "12") (pinfunction "IREF_12") (pintype "bidirectional"))
      (node (ref "R17") (pin "2") (pinfunction "2_2") (pintype "passive"))
    )
    (net (code "41") (name "Net-(Q2-G)") (class "Default")
      (node (ref "D3") (pin "A") (pinfunction "A_A") (pintype "passive"))
      (node (ref "Q2") (pin "4") (pinfunction "G_4") (pintype "passive"))
      (node (ref "Q3") (pin "4") (pinfunction "G_4") (pintype "passive"))
      (node (ref "R10") (pin "2") (pinfunction "2_2") (pintype "passive"))
      (node (ref "R35") (pin "1") (pinfunction "1_1") (pintype "passive"))
    )
    (net (code "42") (name "Net-(Q4-B)") (class "Default")
      (node (ref "Q4") (pin "1") (pinfunction "B_1") (pintype "passive"))
      (node (ref "R11") (pin "1") (pinfunction "1_1") (pintype "passive"))
    )
    (net (code "43") (name "Net-(R7-Pad2)") (class "Default")
      (node (ref "R7") (pin "2") (pinfunction "2_2") (pintype "passive"))
      (node (ref "S3") (pin "1") (pinfunction "1_1") (pintype "passive"))
      (node (ref "S3") (pin "2") (pinfunction "2_2") (pintype "passive"))
    )
    (net (code "44") (name "Net-(U1-VBUS)") (class "Default")
      (node (ref "FB5") (pin "1") (pinfunction "1_1") (pintype "bidirectional"))
      (node (ref "U1") (pin "2") (pinfunction "VBUS_2") (pintype "bidirectional"))
    )
    (net (code "45") (name "Net-(U4-EN)") (class "Default")
      (node (ref "R20") (pin "1") (pinfunction "1_1") (pintype "passive"))
      (node (ref "U4") (pin "4") (pinfunction "EN_4") (pintype "bidirectional"))
    )
    (net (code "46") (name "Net-(U5-VOUT)") (class "Default")
      (node (ref "R41") (pin "2") (pinfunction "2_2") (pintype "passive"))
      (node (ref "U5") (pin "2") (pinfunction "VOUT_2") (pintype "input"))
    )
    (net (code "47") (name "Net-(VD1-P$4)") (class "Default")
      (node (ref "R27") (pin "1") (pinfunction "1_1") (pintype "passive"))
      (node (ref "R4") (pin "1") (pinfunction "1_1") (pintype "passive"))
      (node (ref "R5") (pin "1") (pinfunction "1_1") (pintype "passive"))
      (node (ref "VD1") (pin "4") (pinfunction "P$4_4") (pintype "bidirectional"))
    )
    (net (code "48") (name "Net-(VD1-P$6)") (class "Default")
      (node (ref "R28") (pin "1") (pinfunction "1_1") (pintype "passive"))
      (node (ref "R6") (pin "1") (pinfunction "1_1") (pintype "passive"))
      (node (ref "VD1") (pin "6") (pinfunction "P$6_6") (pintype "bidirectional"))
    )
    (net (code "49") (name "OSC_IN") (class "Default")
      (node (ref "C8") (pin "2") (pinfunction "P$2_2") (pintype "passive"))
      (node (ref "U3") (pin "5") (pinfunction "PF0/OSC_IN_5") (pintype "bidirectional"))
      (node (ref "ZO1") (pin "3") (pinfunction "P$2_3") (pintype "bidirectional"))
    )
    (net (code "50") (name "OSC_OUT") (class "Default")
      (node (ref "C9") (pin "2") (pinfunction "P$2_2") (pintype "passive"))
      (node (ref "U3") (pin "6") (pinfunction "PF1/OSC_OUT\\_6") (pintype "bidirectional"))
      (node (ref "ZO1") (pin "1") (pinfunction "P$1_1") (pintype "bidirectional"))
    )
    (net (code "51") (name "PA0") (class "Default")
      (node (ref "U3") (pin "10") (pinfunction "PA0_10") (pintype "bidirectional"))
    )
    (net (code "52") (name "PA1") (class "Default")
      (node (ref "U3") (pin "11") (pinfunction "PA1_11") (pintype "bidirectional"))
    )
    (net (code "53") (name "PA2{slash}ADC2") (class "Default")
      (node (ref "R41") (pin "1") (pinfunction "1_1") (pintype "passive"))
      (node (ref "U3") (pin "12") (pinfunction "PA2_12") (pintype "bidirectional"))
    )
    (net (code "54") (name "PA3{slash}T2C4") (class "Default")
      (node (ref "C17") (pin "2") (pinfunction "P$2_2") (pintype "passive"))
      (node (ref "U3") (pin "13") (pinfunction "PA3_13") (pintype "bidirectional"))
    )
    (net (code "55") (name "PA4") (class "Default")
      (node (ref "U3") (pin "14") (pinfunction "PA4_14") (pintype "bidirectional"))
    )
    (net (code "56") (name "PA5") (class "Default")
      (node (ref "U3") (pin "15") (pinfunction "PA5_15") (pintype "bidirectional"))
    )
    (net (code "57") (name "PA6") (class "Default")
      (node (ref "U3") (pin "16") (pinfunction "PA6_16") (pintype "bidirectional"))
    )
    (net (code "58") (name "PA7{slash}T1CH1N{slash}T3C2") (class "Default")
      (node (ref "BUZ1") (pin "+") (pinfunction "LEAD+_+") (pintype "passive"))
      (node (ref "U3") (pin "17") (pinfunction "PA7_17") (pintype "bidirectional"))
    )
    (net (code "59") (name "PA8{slash}T1C1") (class "Default")
      (node (ref "U3") (pin "29") (pinfunction "PA8_29") (pintype "bidirectional"))
    )
    (net (code "60") (name "PA9{slash}T1C2") (class "Default")
      (node (ref "U3") (pin "30") (pinfunction "PA9_30") (pintype "bidirectional"))
    )
    (net (code "61") (name "PA10{slash}IT_ACCEL_1") (class "Default")
      (node (ref "U3") (pin "31") (pinfunction "PA10_31") (pintype "bidirectional"))
      (node (ref "U8") (pin "11") (pinfunction "INT1_11") (pintype "bidirectional"))
    )
    (net (code "62") (name "PA11{slash}USB_DM") (class "Default")
      (node (ref "R6") (pin "2") (pinfunction "2_2") (pintype "passive"))
      (node (ref "U3") (pin "32") (pinfunction "PA11_32") (pintype "bidirectional"))
    )
    (net (code "63") (name "PA12{slash}USB_DP") (class "Default")
      (node (ref "R5") (pin "2") (pinfunction "2_2") (pintype "passive"))
      (node (ref "U3") (pin "33") (pinfunction "PA12_33") (pintype "bidirectional"))
    )
    (net (code "64") (name "PA13{slash}SWDIO") (class "Default")
      (node (ref "R27") (pin "2") (pinfunction "2_2") (pintype "passive"))
      (node (ref "U3") (pin "34") (pinfunction "PA13_34") (pintype "bidirectional"))
    )
    (net (code "65") (name "PA14{slash}SWCLK") (class "Default")
      (node (ref "R28") (pin "2") (pinfunction "2_2") (pintype "passive"))
      (node (ref "U3") (pin "37") (pinfunction "PA14_37") (pintype "bidirectional"))
    )
    (net (code "66") (name "PA15") (class "Default")
      (node (ref "U3") (pin "38") (pinfunction "PA15_38") (pintype "bidirectional"))
    )
    (net (code "67") (name "PB0{slash}ADC8") (class "Default")
      (node (ref "R45") (pin "1") (pinfunction "1_1") (pintype "passive"))
      (node (ref "U3") (pin "18") (pinfunction "PB0_18") (pintype "bidirectional"))
    )
    (net (code "68") (name "PB1{slash}IT_FUSB302") (class "Default")
      (node (ref "R16") (pin "2") (pinfunction "2_2") (pintype "passive"))
      (node (ref "U1") (pin "5") (pinfunction "~{INT}_5") (pintype "bidirectional"))
      (node (ref "U3") (pin "19") (pinfunction "PB1_19") (pintype "bidirectional"))
    )
    (net (code "69") (name "PB3{slash}IT_ACCEL_2") (class "Default")
      (node (ref "TP5") (pin "P$1") (pinfunction "1_P$1") (pintype "bidirectional"))
      (node (ref "U3") (pin "39") (pinfunction "PB3_39") (pintype "bidirectional"))
      (node (ref "U8") (pin "9") (pinfunction "INT2_9") (pintype "bidirectional"))
    )
    (net (code "70") (name "PB4") (class "Default")
      (node (ref "U3") (pin "40") (pinfunction "PB4_40") (pintype "bidirectional"))
    )
    (net (code "71") (name "PB5") (class "Default")
      (node (ref "U3") (pin "41") (pinfunction "PB5_41") (pintype "bidirectional"))
    )
    (net (code "72") (name "PB6{slash}SCL1") (class "Default")
      (node (ref "LCD1") (pin "10") (pinfunction "SCL_10") (pintype "bidirectional"))
      (node (ref "R19") (pin "1") (pinfunction "1_1") (pintype "passive"))
      (node (ref "U3") (pin "42") (pinfunction "PB6_42") (pintype "bidirectional"))
    )
    (net (code "73") (name "PB7{slash}SDA1") (class "Default")
      (node (ref "LCD1") (pin "11") (pinfunction "SDA_11") (pintype "bidirectional"))
      (node (ref "R18") (pin "1") (pinfunction "1_1") (pintype "passive"))
      (node (ref "U3") (pin "43") (pinfunction "PB7_43") (pintype "bidirectional"))
    )
    (net (code "74") (name "PB8&BOOT0_S3") (class "Default")
      (node (ref "R7") (pin "1") (pinfunction "1_1") (pintype "passive"))
      (node (ref "R8") (pin "1") (pinfunction "1_1") (pintype "passive"))
      (node (ref "U3") (pin "44") (pinfunction "BOOT0_44") (pintype "bidirectional"))
      (node (ref "U3") (pin "45") (pinfunction "PB8_45") (pintype "bidirectional"))
    )
    (net (code "75") (name "PB9{slash}S1") (class "Default")
      (node (ref "R9") (pin "1") (pinfunction "1_1") (pintype "passive"))
      (node (ref "U3") (pin "46") (pinfunction "PB9_46") (pintype "bidirectional"))
    )
    (net (code "76") (name "PB10{slash}SCL2") (class "Default")
      (node (ref "DA1") (pin "5") (pinfunction "SCL_5") (pintype "bidirectional"))
      (node (ref "R3") (pin "2") (pinfunction "2_2") (pintype "passive"))
      (node (ref "U1") (pin "6") (pinfunction "SCL_6") (pintype "bidirectional"))
      (node (ref "U3") (pin "21") (pinfunction "PB10_21") (pintype "bidirectional"))
      (node (ref "U8") (pin "4") (pinfunction "SCL/SPC_4") (pintype "bidirectional"))
    )
    (net (code "77") (name "PB11{slash}SDA2") (class "Default")
      (node (ref "DA1") (pin "4") (pinfunction "SDA_4") (pintype "bidirectional"))
      (node (ref "R25") (pin "2") (pinfunction "2_2") (pintype "passive"))
      (node (ref "U1") (pin "7") (pinfunction "SDA_7") (pintype "bidirectional"))
      (node (ref "U3") (pin "22") (pinfunction "PB11_22") (pintype "bidirectional"))
      (node (ref "U8") (pin "6") (pinfunction "SDA/SDI_6") (pintype "bidirectional"))
    )
    (net (code "78") (name "PB12") (class "Default")
      (node (ref "U3") (pin "25") (pinfunction "PB12_25") (pintype "bidirectional"))
    )
    (net (code "79") (name "PB13{slash}IT_INA226") (class "Default")
      (node (ref "DA1") (pin "3") (pinfunction "ALERT_3") (pintype "bidirectional"))
      (node (ref "R38") (pin "2") (pinfunction "2_2") (pintype "passive"))
      (node (ref "U3") (pin "26") (pinfunction "PB13_26") (pintype "bidirectional"))
    )
    (net (code "80") (name "PB14{slash}MISO2") (class "Default")
      (node (ref "U3") (pin "27") (pinfunction "PB14_27") (pintype "bidirectional"))
    )
    (net (code "81") (name "PB15{slash}S2") (class "Default")
      (node (ref "R14") (pin "1") (pinfunction "1_1") (pintype "passive"))
      (node (ref "U3") (pin "28") (pinfunction "PB15_28") (pintype "bidirectional"))
    )
    (net (code "82") (name "PC13") (class "Default")
      (node (ref "U3") (pin "2") (pinfunction "PC13_2") (pintype "bidirectional"))
    )
    (net (code "83") (name "PC14{slash}OSC32_IN") (class "Default")
      (node (ref "U3") (pin "3") (pinfunction "PC14/OSC32_IN_3") (pintype "bidirectional"))
    )
    (net (code "84") (name "PC15{slash}OSC32_OUT") (class "Default")
      (node (ref "U3") (pin "4") (pinfunction "PC15/OSC32_OUT_4") (pintype "bidirectional"))
    )
    (net (code "85") (name "PGND") (class "Default")
      (node (ref "CP1") (pin "1A") (pinfunction "P$1_1A") (pintype "bidirectional"))
      (node (ref "CP1") (pin "1B") (pinfunction "P$1_1B") (pintype "bidirectional"))
      (node (ref "PAD10") (pin "TP") (pinfunction "TP_TP") (pintype "input"))
      (node (ref "PAD11") (pin "TP") (pinfunction "TP_TP") (pintype "input"))
      (node (ref "PAD12") (pin "TP") (pinfunction "TP_TP") (pintype "input"))
      (node (ref "PAD9") (pin "TP") (pinfunction "TP_TP") (pintype "input"))
      (node (ref "TP1") (pin "P$1") (pinfunction "P$1_P$1") (pintype "bidirectional"))
    )
    (net (code "86") (name "SAO{slash}SDO{slash}ADDR") (class "Default")
      (node (ref "U8") (pin "7") (pinfunction "SA0/SDO_7") (pintype "bidirectional"))
    )
    (net (code "87") (name "VBUS-C") (class "Default")
      (node (ref "D1") (pin "A") (pinfunction "A_A") (pintype "passive"))
      (node (ref "FB5") (pin "2") (pinfunction "2_2") (pintype "bidirectional"))
      (node (ref "Q2") (pin "5") (pinfunction "D_5") (pintype "passive"))
      (node (ref "Q2") (pin "6") (pinfunction "D_6") (pintype "passive"))
      (node (ref "Q2") (pin "7") (pinfunction "D_7") (pintype "passive"))
      (node (ref "Q2") (pin "8") (pinfunction "D_8") (pintype "passive"))
      (node (ref "Q2") (pin "9") (pinfunction "D_9") (pintype "passive"))
      (node (ref "R10") (pin "1") (pinfunction "1_1") (pintype "passive"))
      (node (ref "R24") (pin "1") (pinfunction "1_1") (pintype "passive"))
      (node (ref "R37") (pin "2") (pinfunction "2_2") (pintype "passive"))
    )
    (net (code "88") (name "unconnected-(J3-SBU1-PadA8)") (class "Default")
      (node (ref "J3") (pin "A8") (pinfunction "SBU1_A8") (pintype "bidirectional"))
    )
    (net (code "89") (name "unconnected-(J3-SBU2-PadB8)") (class "Default")
      (node (ref "J3") (pin "B8") (pinfunction "SBU2_B8") (pintype "bidirectional"))
    )
    (net (code "90") (name "unconnected-(U1-VCONN_01-Pad12)") (class "Default")
      (node (ref "U1") (pin "12") (pinfunction "VCONN_01_12") (pintype "bidirectional"))
    )
    (net (code "91") (name "unconnected-(U1-VCONN_02-Pad13)") (class "Default")
      (node (ref "U1") (pin "13") (pinfunction "VCONN_02_13") (pintype "bidirectional"))
    )
    (net (code "92") (name "unconnected-(VD1-P$5-Pad5)") (class "Default")
      (node (ref "VD1") (pin "5") (pinfunction "P$5_5") (pintype "bidirectional"))
    )
  )
)
